# BME280.net
KiCad netlist of a schematic drawn in Altium Designer
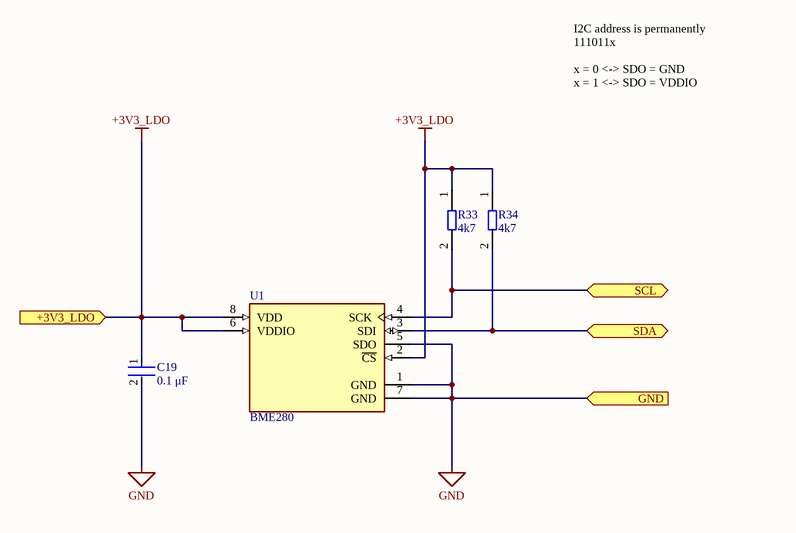
[diagram p0: BME280.SchDoc]

(export (version "E")
  (design (tool "Eeschema 10.0.6"))
  (components
    (comp (ref "C19")
      (value "0.1 μF")
      (footprint "FP-C0805C-DN-MFG")
      (description "C0805 0.10 μF X7R 30ppm/°C 20.00% 50 V C0805C104M5RAC")
      (fields
        (field (name "MANUFACTURER PART NUMBER") "C0805C104M5RAC")
        (field (name "MANUFACTURER") "KEMET")
      )
      (libsource (lib "Altium Content Vault") (part "b4654b650e69147ec39a6b967a45e02"))
    )
    (comp (ref "R33")
      (value "4k7")
      (footprint "0805 Resistor - IPC A")
      (description "Thick Film Resistors - SMD 4.7 kOhms 250 mW 0805 1%\r\nRC0805FR-104K7L")
      (libsource (lib "Callisto Control Board") (part "RC0805FR-104K7L"))
    )
    (comp (ref "R34")
      (value "4k7")
      (footprint "0805 Resistor - IPC A")
      (description "Thick Film Resistors - SMD 4.7 kOhms 250 mW 0805 1%\r\nRC0805FR-104K7L")
      (libsource (lib "Callisto Control Board") (part "RC0805FR-104K7L"))
    )
    (comp (ref "U1")
      (value "BME280")
      (footprint "FP-BME280-MFG")
      (description "SENSOR PRESSURE HUMIDITY TEMP")
      (libsource (lib "Altium Content Vault") (part "d58e2f6669bc67e6a2bc6a28610ca79"))
    )
  )
  (nets
    (net (code "1") (name "+3V3_LDO") (class "Default")
      (node (ref "C19") (pin "1") (pinfunction "1_1") (pintype "passive"))
      (node (ref "R33") (pin "1") (pintype "passive"))
      (node (ref "R34") (pin "1") (pintype "passive"))
      (node (ref "U1") (pin "2") (pinfunction "~{CS}_2") (pintype "input"))
      (node (ref "U1") (pin "6") (pinfunction "VDDIO_6") (pintype "input"))
      (node (ref "U1") (pin "8") (pinfunction "VDD_8") (pintype "input"))
    )
    (net (code "2") (name "/SCL") (class "Default")
      (node (ref "R33") (pin "2") (pintype "passive"))
      (node (ref "U1") (pin "4") (pinfunction "SCK_4") (pintype "input"))
    )
    (net (code "3") (name "/SDA") (class "Default")
      (node (ref "R34") (pin "2") (pintype "passive"))
      (node (ref "U1") (pin "3") (pinfunction "SDI_3") (pintype "bidirectional"))
    )
    (net (code "4") (name "GND") (class "Default")
      (node (ref "C19") (pin "2") (pinfunction "2_2") (pintype "passive"))
      (node (ref "U1") (pin "1") (pinfunction "GND_1") (pintype "passive"))
      (node (ref "U1") (pin "5") (pinfunction "SDO_5") (pintype "passive"))
      (node (ref "U1") (pin "7") (pinfunction "GND_7") (pintype "passive"))
    )
  )
)
